# RT_SUPER_HOST_A.net
KiCad netlist of a schematic drawn in Altium Designer
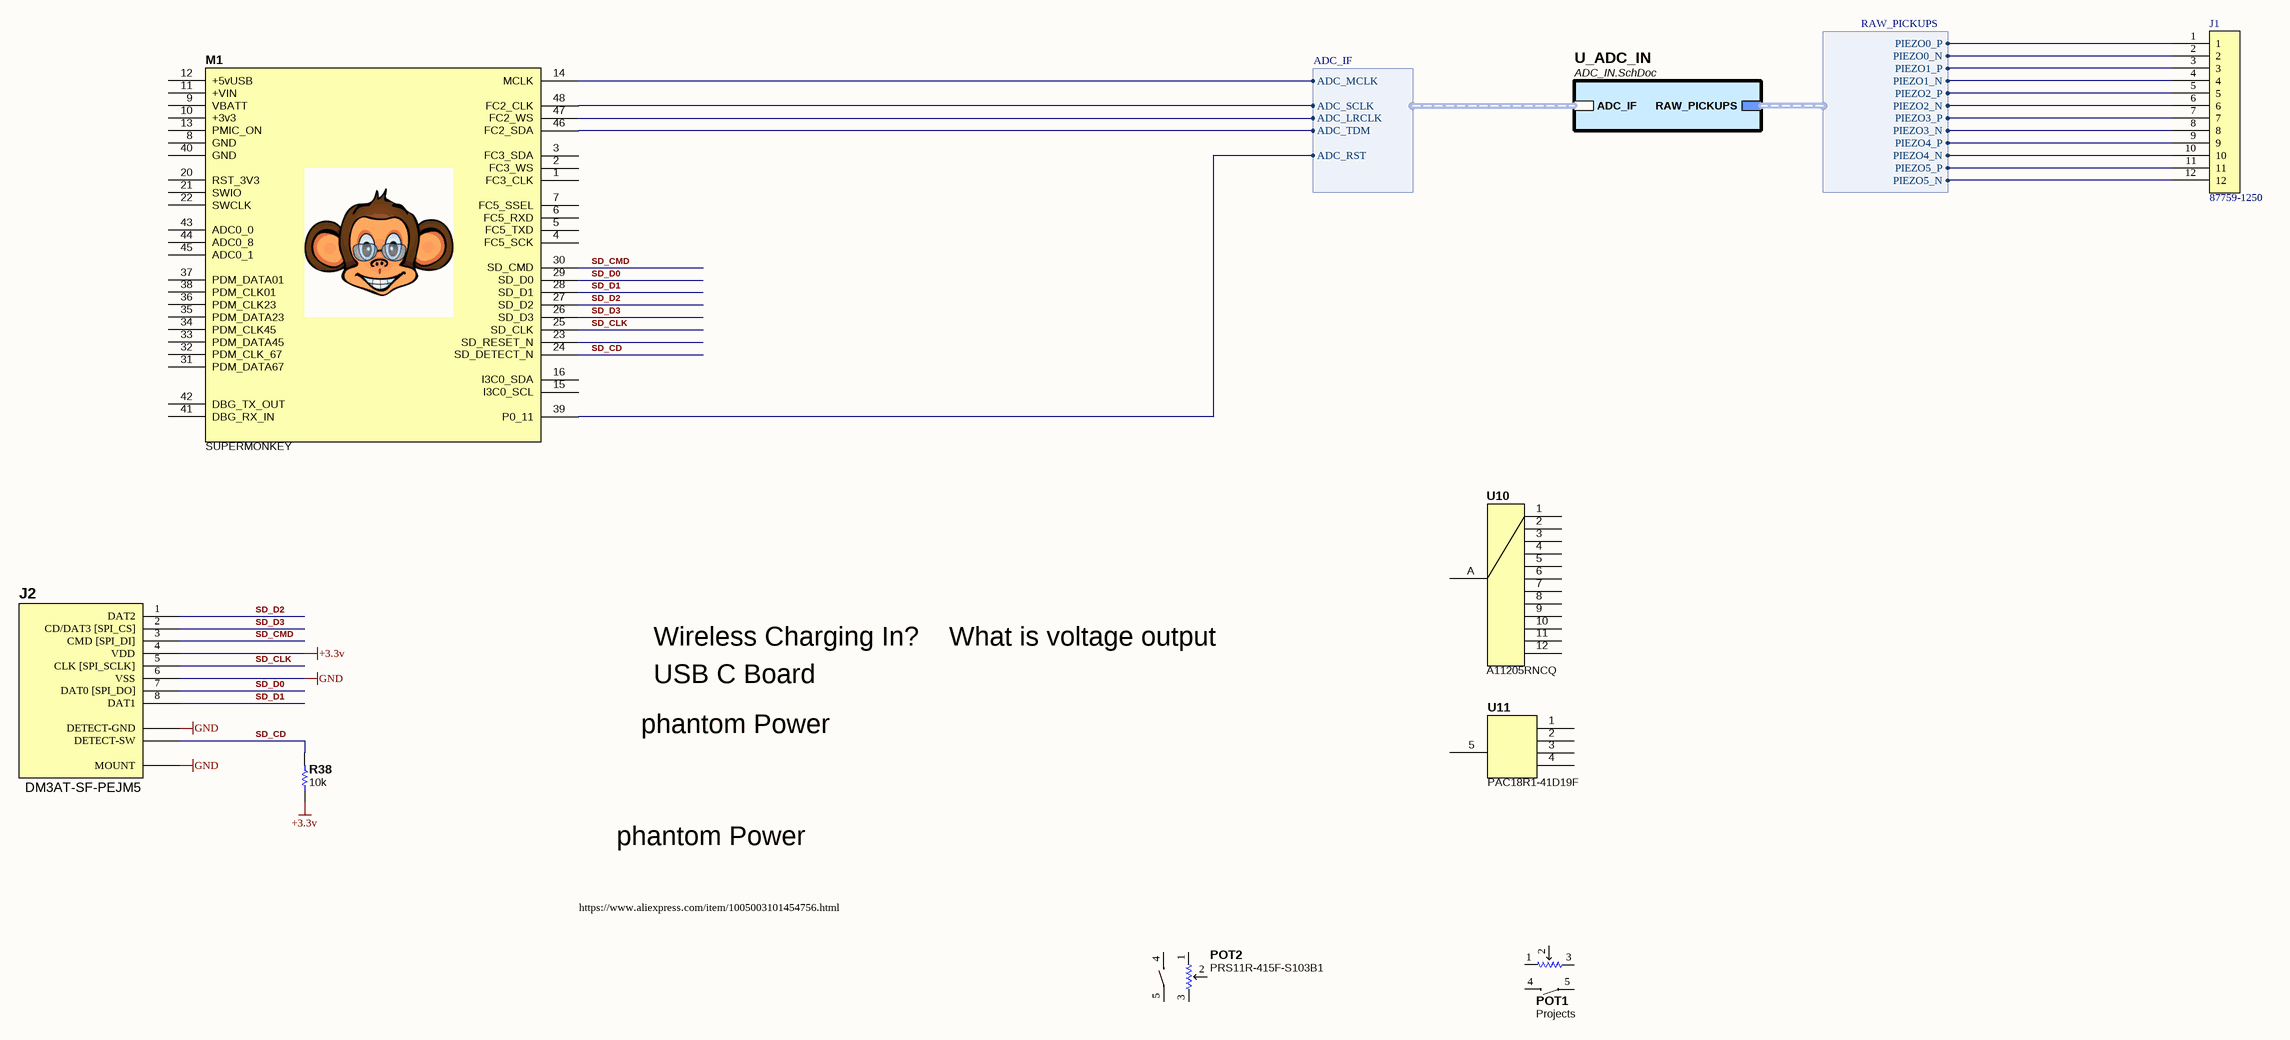
[diagram p0: RT_SUPER_HOST_A.SchDoc]

(export (version "E")
  (design (tool "Eeschema 10.0.6"))
  (components
    (comp (ref "J1")
      (value "87759-1250")
      (footprint "87759-1250")
      (description "CONN HEADER 12POS 2MM VERT SMD")
      (fields (field (name "MANUFACTURER") "Molex Connector Corporation"))
      (libsource (lib "eConnector") (part "87759-1250"))
    )
    (comp (ref "J2")
      (value "DM3AT-SF-PEJM5")
      (footprint "DM3AT-SF-PEJM5")
      (description "CONN MICRO SD R/A PUSH-PUSH SMD")
      (fields (field (name "MANUFACTURER") "Hirose Electric Co Ltd"))
      (libsource (lib "eConnector_SD") (part "DM3AT-SF-PEJM5"))
    )
    (comp (ref "M1")
      (value "SUPERMONKEY")
      (footprint "SUPERMONKEY")
      (libsource (lib "eModule") (part "SUPERMONKEY"))
    )
    (comp (ref "POT1")
      (value "Projects")
      (footprint "PRS11R420FS103B1")
      (fields
        (field (name "MANUFACTURER") "Bourns")
        (field (name "MANUFACTURER PART NUMBER") "PRS11R-415F-S103B1")
      )
      (libsource (lib "ePotentiometer") (part "PRS11R-420F-S103B1"))
    )
    (comp (ref "POT2")
      (value "PRS11R-415F-S103B1")
      (footprint "PRS11R415FS103B1")
      (fields (field (name "MANUFACTURER") "Bourns"))
      (libsource (lib "ePotentiometer") (part "PRS11R-415F-S103B1"))
    )
    (comp (ref "R38")
      (value "10k")
      (footprint "R0402_0.40MM_MD")
      (description "RES 10K OHM 1/10W 1% 0402 SMD")
      (fields
        (field (name "MANUFACTURER PART NUMBER") "ERJ-2RKF1002X")
        (field (name "MANUFACTURER") "Panasonic Electronic Components")
      )
      (libsource (lib "Resistors - Panasonic - AEC-Q200") (part "R_2P"))
    )
    (comp (ref "U10")
      (value "A11205RNCQ")
      (footprint "A11205RNCQ")
      (description "Switch Rotary N.O./N.C. SP12T 12 Flatted Shaft PC Pins 2.5A 125VAC 125VDC Automotive")
      (fields (field (name "MANUFACTURER") "ITT C&K"))
      (libsource (lib "eElectroMechanical") (part "A11205RNCQ"))
    )
    (comp (ref "U11")
      (value "PAC18R1-41D19F")
      (footprint "PAC18R1")
      (fields (field (name "MANUFACTURER") "Bourns"))
      (libsource (lib "eElectroMechanical") (part "PAC18R1-41D19F"))
    )
  )
  (nets
    (net (code "3") (name "+3.3v") (class "Default")
      (node (ref "J2") (pin "4") (pinfunction "VDD_4") (pintype "passive"))
      (node (ref "R38") (pin "1") (pinfunction "1_1") (pintype "passive"))
    )
    (net (code "4") (name "/ADC_LRCLK") (class "Default")
      (node (ref "M1") (pin "47") (pinfunction "FC2_WS_47") (pintype "passive"))
    )
    (net (code "5") (name "/ADC_MCLK") (class "Default")
      (node (ref "M1") (pin "14") (pinfunction "MCLK_14") (pintype "passive"))
    )
    (net (code "6") (name "/ADC_RST") (class "Default")
      (node (ref "M1") (pin "39") (pinfunction "P0_11_39") (pintype "passive"))
    )
    (net (code "7") (name "/ADC_SCLK") (class "Default")
      (node (ref "M1") (pin "48") (pinfunction "FC2_CLK_48") (pintype "passive"))
    )
    (net (code "8") (name "/ADC_TDM") (class "Default")
      (node (ref "M1") (pin "46") (pinfunction "FC2_SDA_46") (pintype "passive"))
    )
    (net (code "9") (name "/PIEZO0_N") (class "Default")
      (node (ref "J1") (pin "2") (pinfunction "2_2") (pintype "passive"))
    )
    (net (code "10") (name "/PIEZO0_P") (class "Default")
      (node (ref "J1") (pin "1") (pinfunction "1_1") (pintype "passive"))
    )
    (net (code "11") (name "/PIEZO1_N") (class "Default")
      (node (ref "J1") (pin "4") (pinfunction "4_4") (pintype "passive"))
    )
    (net (code "12") (name "/PIEZO1_P") (class "Default")
      (node (ref "J1") (pin "3") (pinfunction "3_3") (pintype "passive"))
    )
    (net (code "13") (name "/PIEZO2_N") (class "Default")
      (node (ref "J1") (pin "6") (pinfunction "6_6") (pintype "passive"))
    )
    (net (code "14") (name "/PIEZO2_P") (class "Default")
      (node (ref "J1") (pin "5") (pinfunction "5_5") (pintype "passive"))
    )
    (net (code "15") (name "/PIEZO3_N") (class "Default")
      (node (ref "J1") (pin "8") (pinfunction "8_8") (pintype "passive"))
    )
    (net (code "16") (name "/PIEZO3_P") (class "Default")
      (node (ref "J1") (pin "7") (pinfunction "7_7") (pintype "passive"))
    )
    (net (code "17") (name "/PIEZO4_N") (class "Default")
      (node (ref "J1") (pin "10") (pinfunction "10_10") (pintype "passive"))
    )
    (net (code "18") (name "/PIEZO4_P") (class "Default")
      (node (ref "J1") (pin "9") (pinfunction "9_9") (pintype "passive"))
    )
    (net (code "19") (name "/PIEZO5_N") (class "Default")
      (node (ref "J1") (pin "12") (pinfunction "12_12") (pintype "passive"))
    )
    (net (code "20") (name "/PIEZO5_P") (class "Default")
      (node (ref "J1") (pin "11") (pinfunction "11_11") (pintype "passive"))
    )
    (net (code "21") (name "/SD_CD") (class "Default")
      (node (ref "J2") (pin "CDB") (pinfunction "DETECT-SW_CDB") (pintype "passive"))
      (node (ref "M1") (pin "24") (pinfunction "SD_DETECT_N_24") (pintype "passive"))
      (node (ref "R38") (pin "2") (pinfunction "2_2") (pintype "passive"))
    )
    (net (code "22") (name "/SD_CLK") (class "Default")
      (node (ref "J2") (pin "5") (pinfunction "CLK_[SPI_SCLK]_5") (pintype "passive"))
      (node (ref "M1") (pin "25") (pinfunction "SD_CLK_25") (pintype "passive"))
    )
    (net (code "23") (name "/SD_CMD") (class "Default")
      (node (ref "J2") (pin "3") (pinfunction "CMD_[SPI_DI]_3") (pintype "passive"))
      (node (ref "M1") (pin "30") (pinfunction "SD_CMD_30") (pintype "passive"))
    )
    (net (code "24") (name "/SD_D0") (class "Default")
      (node (ref "J2") (pin "7") (pinfunction "DAT0_[SPI_DO]_7") (pintype "passive"))
      (node (ref "M1") (pin "29") (pinfunction "SD_D0_29") (pintype "passive"))
    )
    (net (code "25") (name "/SD_D1") (class "Default")
      (node (ref "J2") (pin "8") (pinfunction "DAT1_8") (pintype "passive"))
      (node (ref "M1") (pin "28") (pinfunction "SD_D1_28") (pintype "passive"))
    )
    (net (code "26") (name "/SD_D2") (class "Default")
      (node (ref "J2") (pin "1") (pinfunction "DAT2_1") (pintype "passive"))
      (node (ref "M1") (pin "27") (pinfunction "SD_D2_27") (pintype "passive"))
    )
    (net (code "27") (name "/SD_D3") (class "Default")
      (node (ref "J2") (pin "2") (pinfunction "CD/DAT3_[SPI_CS]_2") (pintype "passive"))
      (node (ref "M1") (pin "26") (pinfunction "SD_D3_26") (pintype "passive"))
    )
    (net (code "30") (name "GND") (class "Default")
      (node (ref "J2") (pin "6") (pinfunction "VSS_6") (pintype "passive"))
      (node (ref "J2") (pin "CDA") (pinfunction "DETECT-GND_CDA") (pintype "passive"))
      (node (ref "J2") (pin "M") (pinfunction "MOUNT_M") (pintype "passive"))
    )
    (net (code "31") (name "unconnected-(M1-+3v3-Pad10)") (class "Default")
      (node (ref "M1") (pin "10") (pinfunction "+3v3_10") (pintype "passive"))
    )
    (net (code "32") (name "unconnected-(M1-+5vUSB-Pad12)") (class "Default")
      (node (ref "M1") (pin "12") (pinfunction "+5vUSB_12") (pintype "passive"))
    )
    (net (code "33") (name "unconnected-(M1-+VIN-Pad11)") (class "Default")
      (node (ref "M1") (pin "11") (pinfunction "+VIN_11") (pintype "passive"))
    )
    (net (code "34") (name "unconnected-(M1-ADC0_0-Pad43)") (class "Default")
      (node (ref "M1") (pin "43") (pinfunction "ADC0_0_43") (pintype "passive"))
    )
    (net (code "35") (name "unconnected-(M1-ADC0_1-Pad45)") (class "Default")
      (node (ref "M1") (pin "45") (pinfunction "ADC0_1_45") (pintype "passive"))
    )
    (net (code "36") (name "unconnected-(M1-ADC0_8-Pad44)") (class "Default")
      (node (ref "M1") (pin "44") (pinfunction "ADC0_8_44") (pintype "passive"))
    )
    (net (code "37") (name "unconnected-(M1-DBG_RX_IN-Pad41)") (class "Default")
      (node (ref "M1") (pin "41") (pinfunction "DBG_RX_IN_41") (pintype "passive"))
    )
    (net (code "38") (name "unconnected-(M1-DBG_TX_OUT-Pad42)") (class "Default")
      (node (ref "M1") (pin "42") (pinfunction "DBG_TX_OUT_42") (pintype "passive"))
    )
    (net (code "39") (name "unconnected-(M1-FC3_CLK-Pad1)") (class "Default")
      (node (ref "M1") (pin "1") (pinfunction "FC3_CLK_1") (pintype "passive"))
    )
    (net (code "40") (name "unconnected-(M1-FC3_SDA-Pad3)") (class "Default")
      (node (ref "M1") (pin "3") (pinfunction "FC3_SDA_3") (pintype "passive"))
    )
    (net (code "41") (name "unconnected-(M1-FC3_WS-Pad2)") (class "Default")
      (node (ref "M1") (pin "2") (pinfunction "FC3_WS_2") (pintype "passive"))
    )
    (net (code "42") (name "unconnected-(M1-FC5_RXD-Pad6)") (class "Default")
      (node (ref "M1") (pin "6") (pinfunction "FC5_RXD_6") (pintype "passive"))
    )
    (net (code "43") (name "unconnected-(M1-FC5_SCK-Pad4)") (class "Default")
      (node (ref "M1") (pin "4") (pinfunction "FC5_SCK_4") (pintype "passive"))
    )
    (net (code "44") (name "unconnected-(M1-FC5_SSEL-Pad7)") (class "Default")
      (node (ref "M1") (pin "7") (pinfunction "FC5_SSEL_7") (pintype "passive"))
    )
    (net (code "45") (name "unconnected-(M1-FC5_TXD-Pad5)") (class "Default")
      (node (ref "M1") (pin "5") (pinfunction "FC5_TXD_5") (pintype "passive"))
    )
    (net (code "46") (name "unconnected-(M1-GND-Pad8)") (class "Default")
      (node (ref "M1") (pin "8") (pinfunction "GND_8") (pintype "passive"))
    )
    (net (code "47") (name "unconnected-(M1-GND-Pad40)") (class "Default")
      (node (ref "M1") (pin "40") (pinfunction "GND_40") (pintype "passive"))
    )
    (net (code "48") (name "unconnected-(M1-I3C0_SCL-Pad15)") (class "Default")
      (node (ref "M1") (pin "15") (pinfunction "I3C0_SCL_15") (pintype "passive"))
    )
    (net (code "49") (name "unconnected-(M1-I3C0_SDA-Pad16)") (class "Default")
      (node (ref "M1") (pin "16") (pinfunction "I3C0_SDA_16") (pintype "passive"))
    )
    (net (code "50") (name "unconnected-(M1-PDM_CLK01-Pad38)") (class "Default")
      (node (ref "M1") (pin "38") (pinfunction "PDM_CLK01_38") (pintype "passive"))
    )
    (net (code "51") (name "unconnected-(M1-PDM_CLK23-Pad36)") (class "Default")
      (node (ref "M1") (pin "36") (pinfunction "PDM_CLK23_36") (pintype "passive"))
    )
    (net (code "52") (name "unconnected-(M1-PDM_CLK45-Pad34)") (class "Default")
      (node (ref "M1") (pin "34") (pinfunction "PDM_CLK45_34") (pintype "passive"))
    )
    (net (code "53") (name "unconnected-(M1-PDM_CLK_67-Pad32)") (class "Default")
      (node (ref "M1") (pin "32") (pinfunction "PDM_CLK_67_32") (pintype "passive"))
    )
    (net (code "54") (name "unconnected-(M1-PDM_DATA01-Pad37)") (class "Default")
      (node (ref "M1") (pin "37") (pinfunction "PDM_DATA01_37") (pintype "passive"))
    )
    (net (code "55") (name "unconnected-(M1-PDM_DATA23-Pad35)") (class "Default")
      (node (ref "M1") (pin "35") (pinfunction "PDM_DATA23_35") (pintype "passive"))
    )
    (net (code "56") (name "unconnected-(M1-PDM_DATA45-Pad33)") (class "Default")
      (node (ref "M1") (pin "33") (pinfunction "PDM_DATA45_33") (pintype "passive"))
    )
    (net (code "57") (name "unconnected-(M1-PDM_DATA67-Pad31)") (class "Default")
      (node (ref "M1") (pin "31") (pinfunction "PDM_DATA67_31") (pintype "passive"))
    )
    (net (code "58") (name "unconnected-(M1-PMIC_ON-Pad13)") (class "Default")
      (node (ref "M1") (pin "13") (pinfunction "PMIC_ON_13") (pintype "passive"))
    )
    (net (code "59") (name "unconnected-(M1-RST_3V3-Pad20)") (class "Default")
      (node (ref "M1") (pin "20") (pinfunction "RST_3V3_20") (pintype "passive"))
    )
    (net (code "60") (name "unconnected-(M1-SD_RESET_N-Pad23)") (class "Default")
      (node (ref "M1") (pin "23") (pinfunction "SD_RESET_N_23") (pintype "passive"))
    )
    (net (code "61") (name "unconnected-(M1-SWCLK-Pad22)") (class "Default")
      (node (ref "M1") (pin "22") (pinfunction "SWCLK_22") (pintype "passive"))
    )
    (net (code "62") (name "unconnected-(M1-SWIO-Pad21)") (class "Default")
      (node (ref "M1") (pin "21") (pinfunction "SWIO_21") (pintype "passive"))
    )
    (net (code "63") (name "unconnected-(M1-VBATT-Pad9)") (class "Default")
      (node (ref "M1") (pin "9") (pinfunction "VBATT_9") (pintype "passive"))
    )
    (net (code "64") (name "unconnected-(POT1-Pad1)") (class "Default")
      (node (ref "POT1") (pin "1") (pinfunction "1_1") (pintype "passive"))
    )
    (net (code "65") (name "unconnected-(POT1-Pad2)") (class "Default")
      (node (ref "POT1") (pin "2") (pinfunction "2_2") (pintype "passive"))
    )
    (net (code "66") (name "unconnected-(POT1-Pad3)") (class "Default")
      (node (ref "POT1") (pin "3") (pinfunction "3_3") (pintype "passive"))
    )
    (net (code "67") (name "unconnected-(POT1-Pad4)") (class "Default")
      (node (ref "POT1") (pin "4") (pinfunction "4_4") (pintype "passive"))
    )
    (net (code "68") (name "unconnected-(POT1-Pad5)") (class "Default")
      (node (ref "POT1") (pin "5") (pinfunction "5_5") (pintype "passive"))
    )
    (net (code "69") (name "unconnected-(POT2-Pad1)") (class "Default")
      (node (ref "POT2") (pin "1") (pinfunction "1_1") (pintype "passive"))
    )
    (net (code "70") (name "unconnected-(POT2-Pad2)") (class "Default")
      (node (ref "POT2") (pin "2") (pinfunction "2_2") (pintype "passive"))
    )
    (net (code "71") (name "unconnected-(POT2-Pad3)") (class "Default")
      (node (ref "POT2") (pin "3") (pinfunction "3_3") (pintype "passive"))
    )
    (net (code "72") (name "unconnected-(POT2-Pad4)") (class "Default")
      (node (ref "POT2") (pin "4") (pinfunction "4_4") (pintype "passive"))
    )
    (net (code "73") (name "unconnected-(POT2-Pad5)") (class "Default")
      (node (ref "POT2") (pin "5") (pinfunction "5_5") (pintype "passive"))
    )
    (net (code "74") (name "unconnected-(U10-Pad1)") (class "Default")
      (node (ref "U10") (pin "1") (pinfunction "1_1") (pintype "passive"))
    )
    (net (code "75") (name "unconnected-(U10-Pad2)") (class "Default")
      (node (ref "U10") (pin "2") (pinfunction "2_2") (pintype "passive"))
    )
    (net (code "76") (name "unconnected-(U10-Pad3)") (class "Default")
      (node (ref "U10") (pin "3") (pinfunction "3_3") (pintype "passive"))
    )
    (net (code "77") (name "unconnected-(U10-Pad4)") (class "Default")
      (node (ref "U10") (pin "4") (pinfunction "4_4") (pintype "passive"))
    )
    (net (code "78") (name "unconnected-(U10-Pad5)") (class "Default")
      (node (ref "U10") (pin "5") (pinfunction "5_5") (pintype "passive"))
    )
    (net (code "79") (name "unconnected-(U10-Pad6)") (class "Default")
      (node (ref "U10") (pin "6") (pinfunction "6_6") (pintype "passive"))
    )
    (net (code "80") (name "unconnected-(U10-Pad7)") (class "Default")
      (node (ref "U10") (pin "7") (pinfunction "7_7") (pintype "passive"))
    )
    (net (code "81") (name "unconnected-(U10-Pad8)") (class "Default")
      (node (ref "U10") (pin "8") (pinfunction "8_8") (pintype "passive"))
    )
    (net (code "82") (name "unconnected-(U10-Pad9)") (class "Default")
      (node (ref "U10") (pin "9") (pinfunction "9_9") (pintype "passive"))
    )
    (net (code "83") (name "unconnected-(U10-Pad10)") (class "Default")
      (node (ref "U10") (pin "10") (pinfunction "10_10") (pintype "passive"))
    )
    (net (code "84") (name "unconnected-(U10-Pad11)") (class "Default")
      (node (ref "U10") (pin "11") (pinfunction "11_11") (pintype "passive"))
    )
    (net (code "85") (name "unconnected-(U10-Pad12)") (class "Default")
      (node (ref "U10") (pin "12") (pinfunction "12_12") (pintype "passive"))
    )
    (net (code "86") (name "unconnected-(U10-PadA)") (class "Default")
      (node (ref "U10") (pin "A") (pinfunction "A_A") (pintype "passive"))
    )
    (net (code "87") (name "unconnected-(U11-Pad1)") (class "Default")
      (node (ref "U11") (pin "1") (pinfunction "1_1") (pintype "passive"))
    )
    (net (code "88") (name "unconnected-(U11-Pad2)") (class "Default")
      (node (ref "U11") (pin "2") (pinfunction "2_2") (pintype "passive"))
    )
    (net (code "89") (name "unconnected-(U11-Pad3)") (class "Default")
      (node (ref "U11") (pin "3") (pinfunction "3_3") (pintype "passive"))
    )
    (net (code "90") (name "unconnected-(U11-Pad4)") (class "Default")
      (node (ref "U11") (pin "4") (pinfunction "4_4") (pintype "passive"))
    )
    (net (code "91") (name "unconnected-(U11-Pad5)") (class "Default")
      (node (ref "U11") (pin "5") (pinfunction "5_5") (pintype "passive"))
    )
  )
)
